# I2C-SPI.net
KiCad netlist of a schematic drawn in Altium Designer
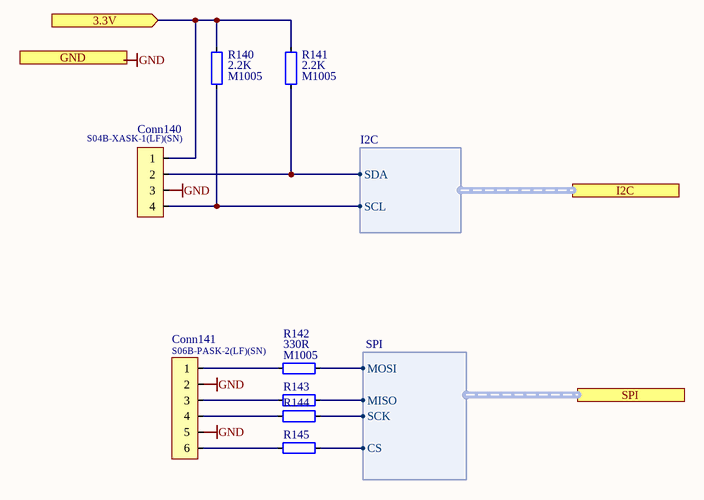
[diagram p0: I2C-SPI.SchDoc]

(export (version "E")
  (design (tool "Eeschema 10.0.6"))
  (components
    (comp (ref "Conn140")
      (value "Connector - 4P")
      (footprint "Connector, S04B-XASK-1")
      (description "Conn, JST, 4P, TH, XA, Side Entry")
      (fields
        (field (name "MANUFACTURER") "JST")
        (field (name "MANUFACTURER PART NUMBER") "S04B-XASK-1(LF)(SN)")
      )
      (libsource (lib "Connector - JST") (part "Connector - 4P"))
    )
    (comp (ref "Conn141")
      (value "Connector - 6P")
      (footprint "Connector, S06B-PASK-2")
      (description "Conn, JST, 6P, TH, PA, Side Entry")
      (fields
        (field (name "MANUFACTURER") "JST")
        (field (name "MANUFACTURER PART NUMBER") "S06B-PASK-2(LF)(SN)")
      )
      (libsource (lib "Connector - JST") (part "Connector - 6P"))
    )
    (comp (ref "R140")
      (value "2.2K")
      (footprint "Resistor_Smd_M1005_I0402")
      (description "Res, 2.2K, 1%, M1005")
      (fields
        (field (name "TOLERANCE") "1%")
        (field (name "MANUFACTURER") "Yageo")
        (field (name "PACKAGE") "M1005")
      )
      (libsource (lib "Resistor") (part "Resistor"))
    )
    (comp (ref "R141")
      (value "2.2K")
      (footprint "Resistor_Smd_M1005_I0402")
      (description "Res, 2.2K, 1%, M1005")
      (fields
        (field (name "TOLERANCE") "1%")
        (field (name "MANUFACTURER") "Yageo")
        (field (name "PACKAGE") "M1005")
      )
      (libsource (lib "Resistor") (part "Resistor"))
    )
    (comp (ref "R142")
      (value "330R")
      (footprint "Resistor_Smd_M1005_I0402")
      (description "Res, 330R, 1%, M1005")
      (fields
        (field (name "TOLERANCE") "1%")
        (field (name "MANUFACTURER") "Yageo")
        (field (name "PACKAGE") "M1005")
      )
      (libsource (lib "Resistor") (part "Resistor"))
    )
    (comp (ref "R143")
      (value "Resistor")
      (footprint "Resistor_Smd_M1005_I0402")
      (description "Res, 330R, 1%, M1005")
      (fields (field (name "TOLERANCE") "1%") (field (name "MANUFACTURER") "Yageo"))
      (libsource (lib "Resistor") (part "Resistor"))
    )
    (comp (ref "R144")
      (value "Resistor")
      (footprint "Resistor_Smd_M1005_I0402")
      (description "Res, 330R, 1%, M1005")
      (fields (field (name "TOLERANCE") "1%") (field (name "MANUFACTURER") "Yageo"))
      (libsource (lib "Resistor") (part "Resistor"))
    )
    (comp (ref "R145")
      (value "Resistor")
      (footprint "Resistor_Smd_M1005_I0402")
      (description "Res, 330R, 1%, M1005")
      (fields (field (name "TOLERANCE") "1%") (field (name "MANUFACTURER") "Yageo"))
      (libsource (lib "Resistor") (part "Resistor"))
    )
  )
  (nets
    (net (code "3") (name "/3.3V") (class "Default")
      (node (ref "Conn140") (pin "1") (pinfunction "1_1") (pintype "passive"))
      (node (ref "R140") (pin "1") (pinfunction "1_1") (pintype "passive"))
      (node (ref "R141") (pin "1") (pinfunction "1_1") (pintype "passive"))
    )
    (net (code "4") (name "/CS") (class "Default")
      (node (ref "R145") (pin "2") (pinfunction "2_2") (pintype "passive"))
    )
    (net (code "5") (name "/MISO") (class "Default")
      (node (ref "R143") (pin "2") (pinfunction "2_2") (pintype "passive"))
    )
    (net (code "6") (name "/MOSI") (class "Default")
      (node (ref "R142") (pin "2") (pinfunction "2_2") (pintype "passive"))
    )
    (net (code "7") (name "/SCK") (class "Default")
      (node (ref "R144") (pin "2") (pinfunction "2_2") (pintype "passive"))
    )
    (net (code "8") (name "/SCL") (class "Default")
      (node (ref "Conn140") (pin "4") (pinfunction "4_4") (pintype "passive"))
      (node (ref "R140") (pin "2") (pinfunction "2_2") (pintype "passive"))
    )
    (net (code "9") (name "/SDA") (class "Default")
      (node (ref "Conn140") (pin "2") (pinfunction "2_2") (pintype "passive"))
      (node (ref "R141") (pin "2") (pinfunction "2_2") (pintype "passive"))
    )
    (net (code "12") (name "GND") (class "Default")
      (node (ref "Conn140") (pin "3") (pinfunction "3_3") (pintype "passive"))
      (node (ref "Conn141") (pin "2") (pinfunction "2_2") (pintype "passive"))
      (node (ref "Conn141") (pin "5") (pinfunction "5_5") (pintype "passive"))
    )
    (net (code "13") (name "Net-(Conn141-Pad1)") (class "Default")
      (node (ref "Conn141") (pin "1") (pinfunction "1_1") (pintype "passive"))
      (node (ref "R142") (pin "1") (pinfunction "1_1") (pintype "passive"))
    )
    (net (code "14") (name "Net-(Conn141-Pad3)") (class "Default")
      (node (ref "Conn141") (pin "3") (pinfunction "3_3") (pintype "passive"))
      (node (ref "R143") (pin "1") (pinfunction "1_1") (pintype "passive"))
    )
    (net (code "15") (name "Net-(Conn141-Pad4)") (class "Default")
      (node (ref "Conn141") (pin "4") (pinfunction "4_4") (pintype "passive"))
      (node (ref "R144") (pin "1") (pinfunction "1_1") (pintype "passive"))
    )
    (net (code "16") (name "Net-(Conn141-Pad6)") (class "Default")
      (node (ref "Conn141") (pin "6") (pinfunction "6_6") (pintype "passive"))
      (node (ref "R145") (pin "1") (pinfunction "1_1") (pintype "passive"))
    )
  )
)
